# Qwiic_Pi_SHIM_double_slot.net
KiCad netlist of a schematic drawn in EAGLE
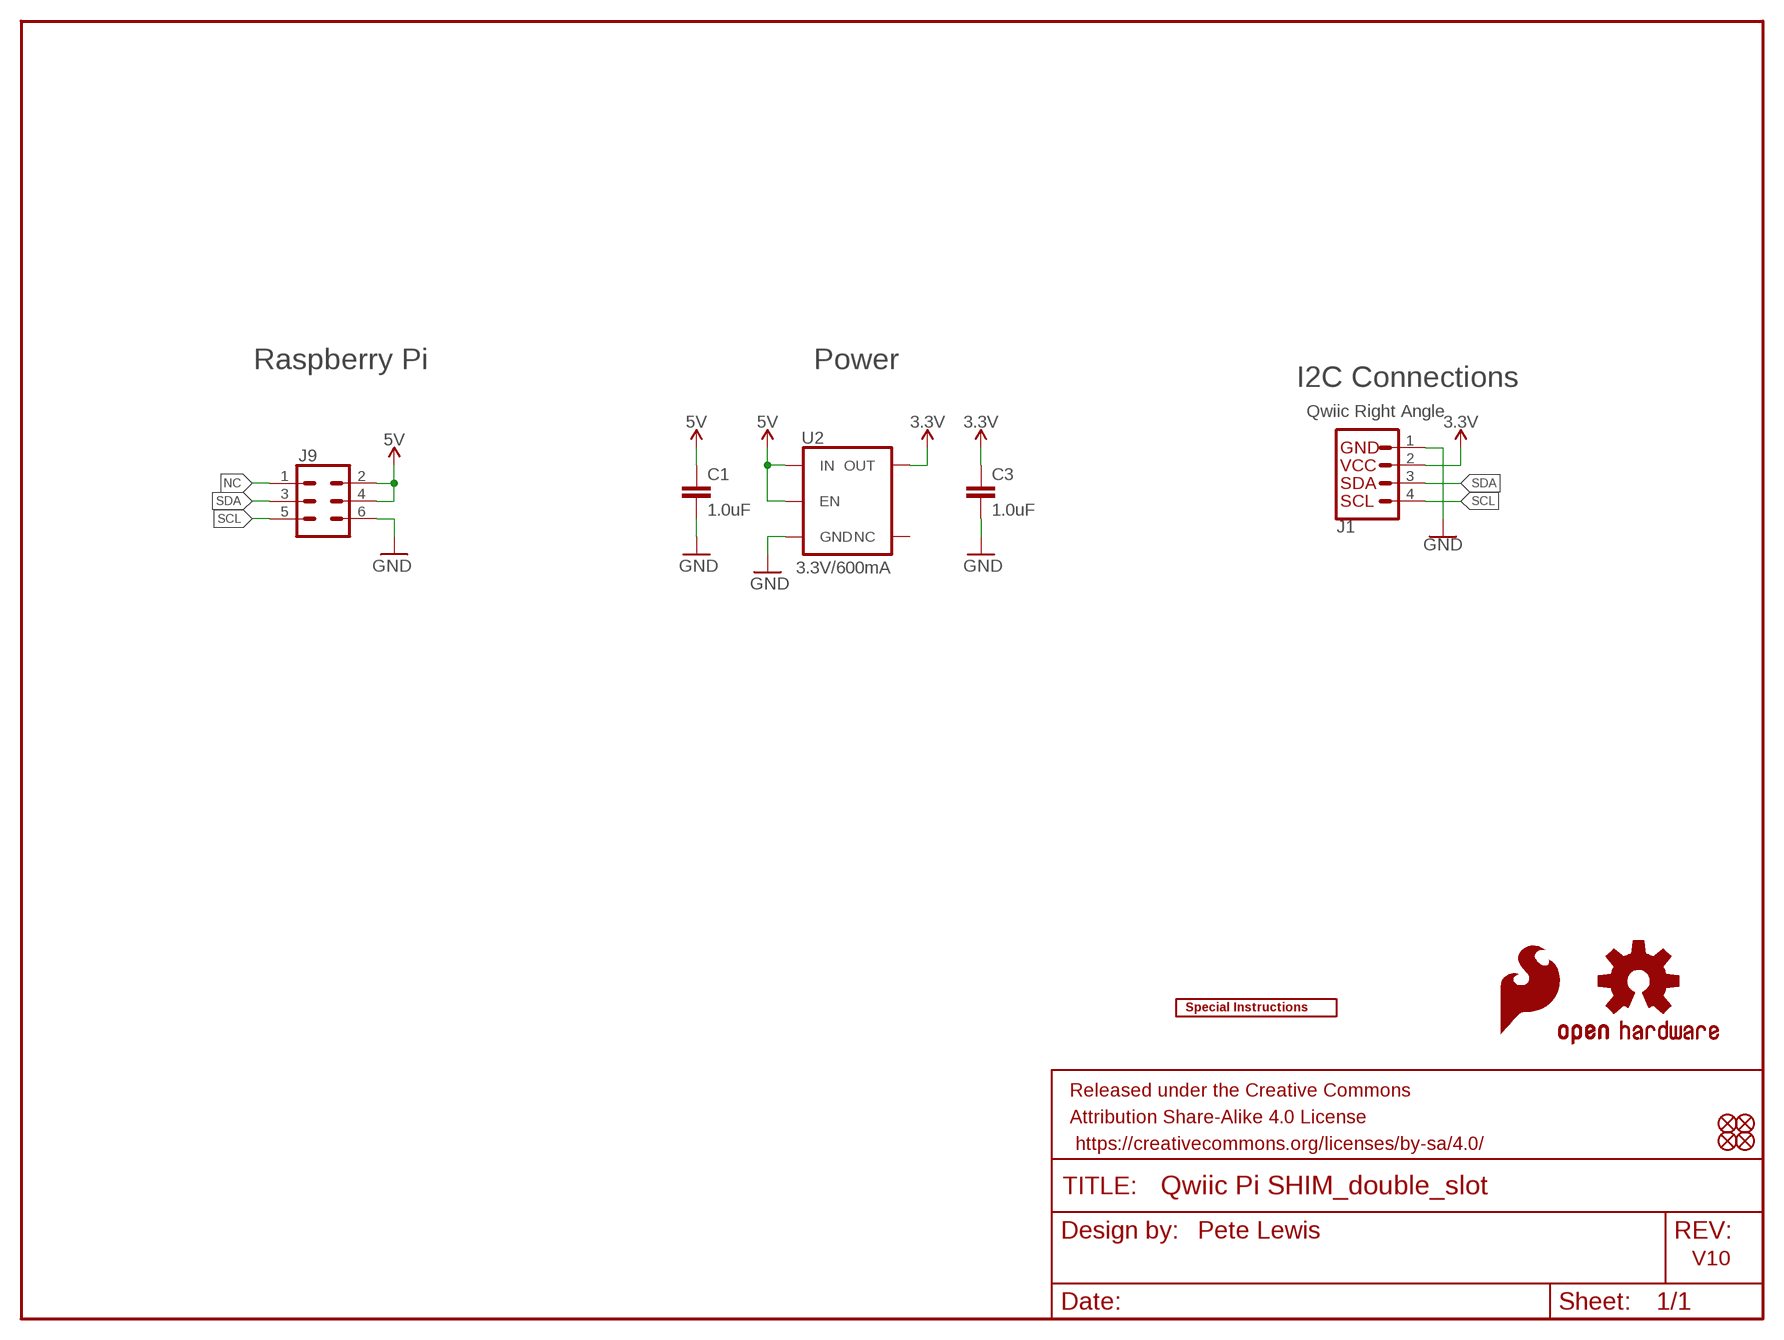
[diagram p0: schematic, sheet 1]

(export (version "E")
  (design (tool "Eeschema 10.0.6"))
  (components
    (comp (ref "C1")
      (value "1.0uF")
      (footprint "eagle-import:0603")
      (libsource (lib "eagle-import") (part "1.0UF-0603-16V-10%"))
    )
    (comp (ref "C3")
      (value "1.0uF")
      (footprint "eagle-import:0603")
      (libsource (lib "eagle-import") (part "1.0UF-0603-16V-10%"))
    )
    (comp (ref "FD1")
      (value "FIDUCIALUFIDUCIAL")
      (footprint "eagle-import:FIDUCIAL-MICRO")
      (libsource (lib "eagle-import") (part "FIDUCIALUFIDUCIAL"))
    )
    (comp (ref "FD2")
      (value "FIDUCIALUFIDUCIAL")
      (footprint "eagle-import:FIDUCIAL-MICRO")
      (libsource (lib "eagle-import") (part "FIDUCIALUFIDUCIAL"))
    )
    (comp (ref "FD3")
      (value "FIDUCIALUFIDUCIAL")
      (footprint "eagle-import:FIDUCIAL-MICRO")
      (libsource (lib "eagle-import") (part "FIDUCIALUFIDUCIAL"))
    )
    (comp (ref "FD4")
      (value "FIDUCIALUFIDUCIAL")
      (footprint "eagle-import:FIDUCIAL-MICRO")
      (libsource (lib "eagle-import") (part "FIDUCIALUFIDUCIAL"))
    )
    (comp (ref "FRAME1")
      (value "FRAME-LETTER")
      (footprint "eagle-import:CREATIVE_COMMONS")
      (libsource (lib "eagle-import") (part "FRAME-LETTER"))
    )
    (comp (ref "J1")
      (value "Qwiic Right Angle")
      (footprint "eagle-import:1X04_1MM_RA")
      (libsource (lib "eagle-import") (part "I2C_STANDARDQWIIC"))
    )
    (comp (ref "J9")
      (value "SPARKFUN-CONNECTORS_CONN_03X2PISHIM_LOCK_SLOTS_DOUBLE")
      (footprint "eagle-import:SPARKFUN-CONNECTORS_2X3-NS_PISHIM_LOCKING_SLOTS_DOUBLE")
      (libsource (lib "eagle-import") (part "SPARKFUN-CONNECTORS_CONN_03X2PISHIM_LOCK_SLOTS_DOUBLE"))
    )
    (comp (ref "LOGO1")
      (value "OSHW-LOGOMINI")
      (footprint "eagle-import:OSHW-LOGO-MINI")
      (libsource (lib "eagle-import") (part "OSHW-LOGOMINI"))
    )
    (comp (ref "U$1")
      (value "SFE_LOGO_FLAME.1_INCH")
      (footprint "eagle-import:SFE_LOGO_FLAME_.1")
      (libsource (lib "eagle-import") (part "SFE_LOGO_FLAME.1_INCH"))
    )
    (comp (ref "U$4")
      (value "SPECIAL_INSTRUCTIONS-ORDERING")
      (footprint "eagle-import:ORDERING_INSTRUCTIONS")
      (libsource (lib "eagle-import") (part "SPECIAL_INSTRUCTIONS-ORDERING"))
    )
    (comp (ref "U2")
      (value "3.3V/600mA")
      (footprint "eagle-import:SOT23-5")
      (libsource (lib "eagle-import") (part "V_REG_AP2112K-3.3V"))
    )
  )
  (nets
    (net (code "1") (name "3.3V") (class "Default")
      (node (ref "C3") (pin "1") (pinfunction "1_1") (pintype "passive"))
      (node (ref "J1") (pin "2") (pinfunction "2_2") (pintype "power_in"))
      (node (ref "U2") (pin "5") (pinfunction "OUT_5") (pintype "passive"))
    )
    (net (code "2") (name "5V") (class "Default")
      (node (ref "C1") (pin "1") (pinfunction "1_1") (pintype "passive"))
      (node (ref "J9") (pin "2") (pinfunction "2_2") (pintype "bidirectional"))
      (node (ref "J9") (pin "4") (pinfunction "4_4") (pintype "bidirectional"))
      (node (ref "U2") (pin "1") (pinfunction "IN_1") (pintype "input"))
      (node (ref "U2") (pin "3") (pinfunction "EN_3") (pintype "input"))
    )
    (net (code "3") (name "GND") (class "Default")
      (node (ref "C1") (pin "2") (pinfunction "2_2") (pintype "passive"))
      (node (ref "C3") (pin "2") (pinfunction "2_2") (pintype "passive"))
      (node (ref "J1") (pin "1") (pinfunction "1_1") (pintype "power_in"))
      (node (ref "J9") (pin "6") (pinfunction "6_6") (pintype "bidirectional"))
      (node (ref "U2") (pin "2") (pinfunction "GND_2") (pintype "input"))
    )
    (net (code "4") (name "NC") (class "Default")
      (node (ref "J9") (pin "1") (pinfunction "1_1") (pintype "bidirectional"))
    )
    (net (code "5") (name "SCL") (class "Default")
      (node (ref "J1") (pin "4") (pinfunction "4_4") (pintype "passive"))
      (node (ref "J9") (pin "5") (pinfunction "5_5") (pintype "bidirectional"))
    )
    (net (code "6") (name "SDA") (class "Default")
      (node (ref "J1") (pin "3") (pinfunction "3_3") (pintype "passive"))
      (node (ref "J9") (pin "3") (pinfunction "3_3") (pintype "bidirectional"))
    )
    (net (code "7") (name "unconnected-(U2-NC-Pad4)") (class "Default")
      (node (ref "U2") (pin "4") (pinfunction "NC_4") (pintype "no_connect"))
    )
  )
)
